# LOCO-Light.net
KiCad netlist of a schematic drawn in EAGLE
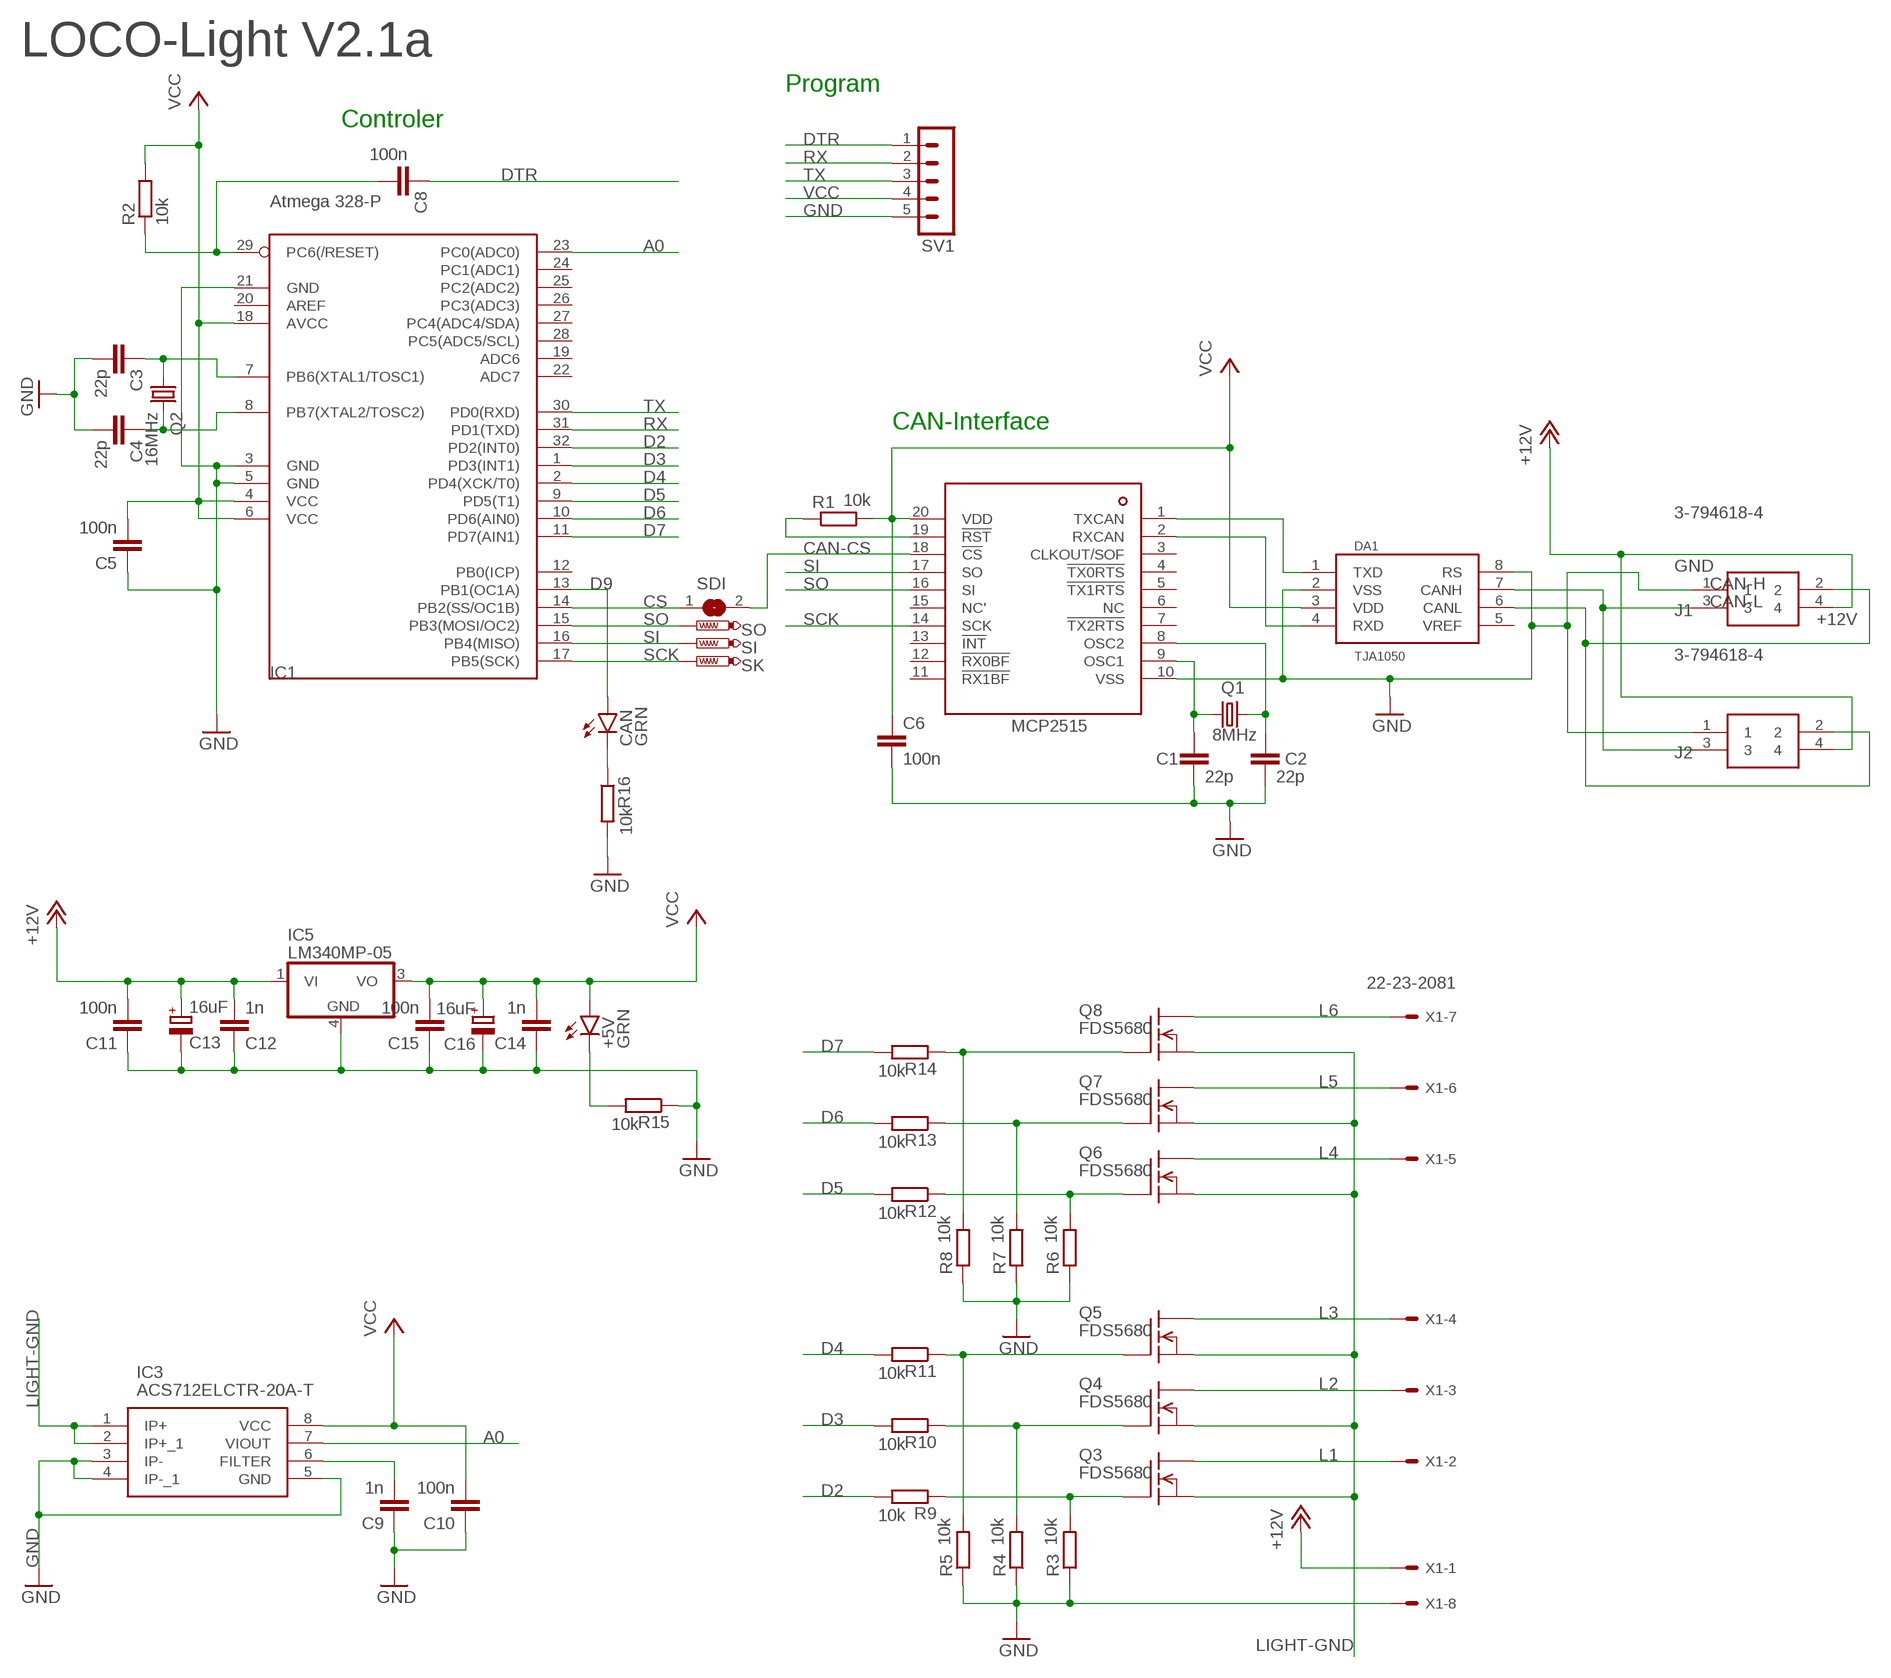
[diagram p0: schematic, sheet 1]

(export (version "E")
  (design (tool "Eeschema 10.0.6"))
  (components
    (comp (ref "+5V")
      (value "GRN")
      (footprint "eagle-import:CHIP-LED0603")
      (libsource (lib "eagle-import") (part "LEDCHIP-LED0603"))
    )
    (comp (ref "C1")
      (value "22p")
      (footprint "eagle-import:C0402K")
      (libsource (lib "eagle-import") (part "C-EUC0402K"))
    )
    (comp (ref "C2")
      (value "22p")
      (footprint "eagle-import:C0402K")
      (libsource (lib "eagle-import") (part "C-EUC0402K"))
    )
    (comp (ref "C3")
      (value "22p")
      (footprint "eagle-import:C0402K")
      (libsource (lib "eagle-import") (part "C-EUC0402K"))
    )
    (comp (ref "C4")
      (value "22p")
      (footprint "eagle-import:C0402K")
      (libsource (lib "eagle-import") (part "C-EUC0402K"))
    )
    (comp (ref "C5")
      (value "100n")
      (footprint "eagle-import:C0402K")
      (libsource (lib "eagle-import") (part "C-EUC0402K"))
    )
    (comp (ref "C6")
      (value "100n")
      (footprint "eagle-import:C0402K")
      (libsource (lib "eagle-import") (part "C-EUC0402K"))
    )
    (comp (ref "C8")
      (value "100n")
      (footprint "eagle-import:C0402K")
      (libsource (lib "eagle-import") (part "C-EUC0402K"))
    )
    (comp (ref "C9")
      (value "1n")
      (footprint "eagle-import:C0402K")
      (libsource (lib "eagle-import") (part "C-EUC0402K"))
    )
    (comp (ref "C10")
      (value "100n")
      (footprint "eagle-import:C0402K")
      (libsource (lib "eagle-import") (part "C-EUC0402K"))
    )
    (comp (ref "C11")
      (value "100n")
      (footprint "eagle-import:C0402K")
      (libsource (lib "eagle-import") (part "C-EUC0402K"))
    )
    (comp (ref "C12")
      (value "1n")
      (footprint "eagle-import:C0402K")
      (libsource (lib "eagle-import") (part "C-EUC0402K"))
    )
    (comp (ref "C13")
      (value "16uF")
      (footprint "eagle-import:A_3216-18W")
      (libsource (lib "eagle-import") (part "CPOL-EUA/3216-18W"))
    )
    (comp (ref "C14")
      (value "1n")
      (footprint "eagle-import:C0402K")
      (libsource (lib "eagle-import") (part "C-EUC0402K"))
    )
    (comp (ref "C15")
      (value "100n")
      (footprint "eagle-import:C0402K")
      (libsource (lib "eagle-import") (part "C-EUC0402K"))
    )
    (comp (ref "C16")
      (value "16uF")
      (footprint "eagle-import:A_3216-18W")
      (libsource (lib "eagle-import") (part "CPOL-EUA/3216-18W"))
    )
    (comp (ref "CAN")
      (value "GRN")
      (footprint "eagle-import:CHIP-LED0603")
      (libsource (lib "eagle-import") (part "LEDCHIP-LED0603"))
    )
    (comp (ref "DA1")
      (value "TJA1050")
      (footprint "eagle-import:SO08")
      (libsource (lib "eagle-import") (part "TJA1050"))
    )
    (comp (ref "IC1")
      (value "Atmega 328-P")
      (footprint "eagle-import:TQFP32-08")
      (fields (field (name "MPN") "ATMEGA8-16AU"))
      (libsource (lib "eagle-import") (part "MEGA8-AI"))
    )
    (comp (ref "IC2")
      (value "MCP2515")
      (footprint "eagle-import:TSSOP20")
      (libsource (lib "eagle-import") (part "MCP2515"))
    )
    (comp (ref "IC3")
      (value "ACS712ELCTR-20A-T")
      (footprint "eagle-import:SOIC127P600X175-8N")
      (fields (field (name "RS_PART_NUMBER") "6807135P"))
      (libsource (lib "eagle-import") (part "ACS712ELCTR-20A-T"))
    )
    (comp (ref "IC5")
      (value "LM340MP-05")
      (footprint "eagle-import:SOT223")
      (libsource (lib "eagle-import") (part "LM340?-MP05"))
    )
    (comp (ref "J1")
      (value "3-794618-4")
      (footprint "eagle-import:SHDRRA4W102P300_2X2_686X892X73")
      (libsource (lib "eagle-import") (part "3-794618-4"))
    )
    (comp (ref "J2")
      (value "3-794618-4")
      (footprint "eagle-import:SHDRRA4W102P300_2X2_686X892X73")
      (libsource (lib "eagle-import") (part "3-794618-4"))
    )
    (comp (ref "Q1")
      (value "8MHz")
      (footprint "eagle-import:HC49_S")
      (libsource (lib "eagle-import") (part "CRYSTALHC49S"))
    )
    (comp (ref "Q2")
      (value "16MHz")
      (footprint "eagle-import:HC49_S")
      (libsource (lib "eagle-import") (part "CRYSTALHC49S"))
    )
    (comp (ref "Q3")
      (value "FDS5680")
      (footprint "eagle-import:SO-8")
      (libsource (lib "eagle-import") (part "FDS5680"))
    )
    (comp (ref "Q4")
      (value "FDS5680")
      (footprint "eagle-import:SO-8")
      (libsource (lib "eagle-import") (part "FDS5680"))
    )
    (comp (ref "Q5")
      (value "FDS5680")
      (footprint "eagle-import:SO-8")
      (libsource (lib "eagle-import") (part "FDS5680"))
    )
    (comp (ref "Q6")
      (value "FDS5680")
      (footprint "eagle-import:SO-8")
      (libsource (lib "eagle-import") (part "FDS5680"))
    )
    (comp (ref "Q7")
      (value "FDS5680")
      (footprint "eagle-import:SO-8")
      (libsource (lib "eagle-import") (part "FDS5680"))
    )
    (comp (ref "Q8")
      (value "FDS5680")
      (footprint "eagle-import:SO-8")
      (libsource (lib "eagle-import") (part "FDS5680"))
    )
    (comp (ref "R1")
      (value "10k")
      (footprint "eagle-import:R0603")
      (libsource (lib "eagle-import") (part "R-EU_R0603"))
    )
    (comp (ref "R2")
      (value "10k")
      (footprint "eagle-import:R0603")
      (libsource (lib "eagle-import") (part "R-EU_R0603"))
    )
    (comp (ref "R3")
      (value "10k")
      (footprint "eagle-import:R0603")
      (libsource (lib "eagle-import") (part "R-EU_R0603"))
    )
    (comp (ref "R4")
      (value "10k")
      (footprint "eagle-import:R0603")
      (libsource (lib "eagle-import") (part "R-EU_R0603"))
    )
    (comp (ref "R5")
      (value "10k")
      (footprint "eagle-import:R0603")
      (libsource (lib "eagle-import") (part "R-EU_R0603"))
    )
    (comp (ref "R6")
      (value "10k")
      (footprint "eagle-import:R0603")
      (libsource (lib "eagle-import") (part "R-EU_R0603"))
    )
    (comp (ref "R7")
      (value "10k")
      (footprint "eagle-import:R0603")
      (libsource (lib "eagle-import") (part "R-EU_R0603"))
    )
    (comp (ref "R8")
      (value "10k")
      (footprint "eagle-import:R0603")
      (libsource (lib "eagle-import") (part "R-EU_R0603"))
    )
    (comp (ref "R9")
      (value "10k")
      (footprint "eagle-import:R0603")
      (libsource (lib "eagle-import") (part "R-EU_R0603"))
    )
    (comp (ref "R10")
      (value "10k")
      (footprint "eagle-import:R0603")
      (libsource (lib "eagle-import") (part "R-EU_R0603"))
    )
    (comp (ref "R11")
      (value "10k")
      (footprint "eagle-import:R0603")
      (libsource (lib "eagle-import") (part "R-EU_R0603"))
    )
    (comp (ref "R12")
      (value "10k")
      (footprint "eagle-import:R0603")
      (libsource (lib "eagle-import") (part "R-EU_R0603"))
    )
    (comp (ref "R13")
      (value "10k")
      (footprint "eagle-import:R0603")
      (libsource (lib "eagle-import") (part "R-EU_R0603"))
    )
    (comp (ref "R14")
      (value "10k")
      (footprint "eagle-import:R0603")
      (libsource (lib "eagle-import") (part "R-EU_R0603"))
    )
    (comp (ref "R15")
      (value "10k")
      (footprint "eagle-import:R0603")
      (libsource (lib "eagle-import") (part "R-EU_R0603"))
    )
    (comp (ref "R16")
      (value "10k")
      (footprint "eagle-import:R0603")
      (libsource (lib "eagle-import") (part "R-EU_R0603"))
    )
    (comp (ref "SDI") (value "SJ") (footprint "eagle-import:SJ") (libsource (lib "eagle-import") (part "SJ")))
    (comp (ref "SI")
      (value "PTR1B1,27")
      (footprint "eagle-import:B1,27")
      (libsource (lib "eagle-import") (part "PTR1B1,27"))
    )
    (comp (ref "SK")
      (value "PTR1B1,27")
      (footprint "eagle-import:B1,27")
      (libsource (lib "eagle-import") (part "PTR1B1,27"))
    )
    (comp (ref "SO")
      (value "PTR1B1,27")
      (footprint "eagle-import:B1,27")
      (libsource (lib "eagle-import") (part "PTR1B1,27"))
    )
    (comp (ref "SV1")
      (value "MA05-1")
      (footprint "eagle-import:MA05-1")
      (libsource (lib "eagle-import") (part "MA05-1"))
    )
    (comp (ref "X1")
      (value "22-23-2081")
      (footprint "eagle-import:22-23-2081")
      (fields (field (name "MF") "MOLEX"))
      (libsource (lib "eagle-import") (part "22-23-2081"))
    )
  )
  (nets
    (net (code "1") (name "+12V") (class "Default")
      (node (ref "C11") (pin "2") (pinfunction "2_2") (pintype "passive"))
      (node (ref "C12") (pin "2") (pinfunction "2_2") (pintype "passive"))
      (node (ref "C13") (pin "+") (pinfunction "+_+") (pintype "passive"))
      (node (ref "IC5") (pin "1") (pinfunction "VI_1") (pintype "input"))
      (node (ref "J1") (pin "4") (pinfunction "4_4") (pintype "bidirectional"))
      (node (ref "J2") (pin "4") (pinfunction "4_4") (pintype "bidirectional"))
      (node (ref "X1") (pin "1") (pinfunction "S_1") (pintype "passive"))
    )
    (net (code "2") (name "A0") (class "Default")
      (node (ref "IC1") (pin "23") (pinfunction "PC0(ADC0)_23") (pintype "bidirectional"))
      (node (ref "IC3") (pin "7") (pinfunction "VIOUT_7") (pintype "bidirectional"))
    )
    (net (code "3") (name "CAN-CS") (class "Default")
      (node (ref "IC2") (pin "18") (pinfunction "~{CS}_18") (pintype "bidirectional"))
      (node (ref "SDI") (pin "2") (pinfunction "2_2") (pintype "passive"))
    )
    (net (code "4") (name "CAN-H") (class "Default")
      (node (ref "DA1") (pin "7") (pinfunction "CANH_7") (pintype "bidirectional"))
      (node (ref "J1") (pin "3") (pinfunction "3_3") (pintype "bidirectional"))
      (node (ref "J2") (pin "3") (pinfunction "3_3") (pintype "bidirectional"))
    )
    (net (code "5") (name "CAN-L") (class "Default")
      (node (ref "DA1") (pin "6") (pinfunction "CANL_6") (pintype "bidirectional"))
      (node (ref "J1") (pin "2") (pinfunction "2_2") (pintype "bidirectional"))
      (node (ref "J2") (pin "2") (pinfunction "2_2") (pintype "bidirectional"))
    )
    (net (code "6") (name "CS") (class "Default")
      (node (ref "IC1") (pin "14") (pinfunction "PB2(SS/OC1B)_14") (pintype "bidirectional"))
      (node (ref "SDI") (pin "1") (pinfunction "1_1") (pintype "passive"))
    )
    (net (code "7") (name "D2") (class "Default")
      (node (ref "IC1") (pin "32") (pinfunction "PD2(INT0)_32") (pintype "bidirectional"))
      (node (ref "R9") (pin "2") (pinfunction "2_2") (pintype "passive"))
    )
    (net (code "8") (name "D3") (class "Default")
      (node (ref "IC1") (pin "1") (pinfunction "PD3(INT1)_1") (pintype "bidirectional"))
      (node (ref "R10") (pin "2") (pinfunction "2_2") (pintype "passive"))
    )
    (net (code "9") (name "D4") (class "Default")
      (node (ref "IC1") (pin "2") (pinfunction "PD4(XCK/T0)_2") (pintype "bidirectional"))
      (node (ref "R11") (pin "2") (pinfunction "2_2") (pintype "passive"))
    )
    (net (code "10") (name "D5") (class "Default")
      (node (ref "IC1") (pin "9") (pinfunction "PD5(T1)_9") (pintype "bidirectional"))
      (node (ref "R12") (pin "2") (pinfunction "2_2") (pintype "passive"))
    )
    (net (code "11") (name "D6") (class "Default")
      (node (ref "IC1") (pin "10") (pinfunction "PD6(AIN0)_10") (pintype "bidirectional"))
      (node (ref "R13") (pin "2") (pinfunction "2_2") (pintype "passive"))
    )
    (net (code "12") (name "D7") (class "Default")
      (node (ref "IC1") (pin "11") (pinfunction "PD7(AIN1)_11") (pintype "bidirectional"))
      (node (ref "R14") (pin "2") (pinfunction "2_2") (pintype "passive"))
    )
    (net (code "13") (name "D9") (class "Default")
      (node (ref "CAN") (pin "A") (pinfunction "A_A") (pintype "passive"))
      (node (ref "IC1") (pin "13") (pinfunction "PB1(OC1A)_13") (pintype "bidirectional"))
    )
    (net (code "14") (name "DTR") (class "Default")
      (node (ref "C8") (pin "1") (pinfunction "1_1") (pintype "passive"))
      (node (ref "SV1") (pin "1") (pinfunction "1_1") (pintype "passive"))
    )
    (net (code "15") (name "GND") (class "Default")
      (node (ref "C1") (pin "2") (pinfunction "2_2") (pintype "passive"))
      (node (ref "C10") (pin "1") (pinfunction "1_1") (pintype "passive"))
      (node (ref "C11") (pin "1") (pinfunction "1_1") (pintype "passive"))
      (node (ref "C12") (pin "1") (pinfunction "1_1") (pintype "passive"))
      (node (ref "C13") (pin "-") (pinfunction "-_-") (pintype "passive"))
      (node (ref "C14") (pin "1") (pinfunction "1_1") (pintype "passive"))
      (node (ref "C15") (pin "1") (pinfunction "1_1") (pintype "passive"))
      (node (ref "C16") (pin "-") (pinfunction "-_-") (pintype "passive"))
      (node (ref "C2") (pin "2") (pinfunction "2_2") (pintype "passive"))
      (node (ref "C3") (pin "2") (pinfunction "2_2") (pintype "passive"))
      (node (ref "C4") (pin "2") (pinfunction "2_2") (pintype "passive"))
      (node (ref "C5") (pin "1") (pinfunction "1_1") (pintype "passive"))
      (node (ref "C6") (pin "2") (pinfunction "2_2") (pintype "passive"))
      (node (ref "C9") (pin "1") (pinfunction "1_1") (pintype "passive"))
      (node (ref "DA1") (pin "2") (pinfunction "VSS_2") (pintype "power_in"))
      (node (ref "DA1") (pin "8") (pinfunction "RS_8") (pintype "input"))
      (node (ref "IC1") (pin "21") (pinfunction "GND_21") (pintype "power_in"))
      (node (ref "IC1") (pin "3") (pinfunction "GND_3") (pintype "power_in"))
      (node (ref "IC1") (pin "5") (pinfunction "GND_5") (pintype "power_in"))
      (node (ref "IC2") (pin "10") (pinfunction "VSS_10") (pintype "bidirectional"))
      (node (ref "IC3") (pin "3") (pinfunction "IP-_3") (pintype "bidirectional"))
      (node (ref "IC3") (pin "4") (pinfunction "IP-_1_4") (pintype "bidirectional"))
      (node (ref "IC3") (pin "5") (pinfunction "GND_5") (pintype "power_in"))
      (node (ref "IC5") (pin "4") (pinfunction "GND_4") (pintype "passive"))
      (node (ref "J1") (pin "1") (pinfunction "1_1") (pintype "bidirectional"))
      (node (ref "J2") (pin "1") (pinfunction "1_1") (pintype "bidirectional"))
      (node (ref "R15") (pin "1") (pinfunction "1_1") (pintype "passive"))
      (node (ref "R16") (pin "2") (pinfunction "2_2") (pintype "passive"))
      (node (ref "R3") (pin "1") (pinfunction "1_1") (pintype "passive"))
      (node (ref "R4") (pin "1") (pinfunction "1_1") (pintype "passive"))
      (node (ref "R5") (pin "1") (pinfunction "1_1") (pintype "passive"))
      (node (ref "R6") (pin "1") (pinfunction "1_1") (pintype "passive"))
      (node (ref "R7") (pin "1") (pinfunction "1_1") (pintype "passive"))
      (node (ref "R8") (pin "1") (pinfunction "1_1") (pintype "passive"))
      (node (ref "SV1") (pin "5") (pinfunction "5_5") (pintype "passive"))
      (node (ref "X1") (pin "8") (pinfunction "S_8") (pintype "passive"))
    )
    (net (code "16") (name "L1") (class "Default")
      (node (ref "Q3") (pin "5") (pinfunction "D_5") (pintype "passive"))
      (node (ref "Q3") (pin "6") (pinfunction "D_6") (pintype "passive"))
      (node (ref "Q3") (pin "7") (pinfunction "D_7") (pintype "passive"))
      (node (ref "Q3") (pin "8") (pinfunction "D_8") (pintype "passive"))
      (node (ref "X1") (pin "2") (pinfunction "S_2") (pintype "passive"))
    )
    (net (code "17") (name "L2") (class "Default")
      (node (ref "Q4") (pin "5") (pinfunction "D_5") (pintype "passive"))
      (node (ref "Q4") (pin "6") (pinfunction "D_6") (pintype "passive"))
      (node (ref "Q4") (pin "7") (pinfunction "D_7") (pintype "passive"))
      (node (ref "Q4") (pin "8") (pinfunction "D_8") (pintype "passive"))
      (node (ref "X1") (pin "3") (pinfunction "S_3") (pintype "passive"))
    )
    (net (code "18") (name "L3") (class "Default")
      (node (ref "Q5") (pin "5") (pinfunction "D_5") (pintype "passive"))
      (node (ref "Q5") (pin "6") (pinfunction "D_6") (pintype "passive"))
      (node (ref "Q5") (pin "7") (pinfunction "D_7") (pintype "passive"))
      (node (ref "Q5") (pin "8") (pinfunction "D_8") (pintype "passive"))
      (node (ref "X1") (pin "4") (pinfunction "S_4") (pintype "passive"))
    )
    (net (code "19") (name "L4") (class "Default")
      (node (ref "Q6") (pin "5") (pinfunction "D_5") (pintype "passive"))
      (node (ref "Q6") (pin "6") (pinfunction "D_6") (pintype "passive"))
      (node (ref "Q6") (pin "7") (pinfunction "D_7") (pintype "passive"))
      (node (ref "Q6") (pin "8") (pinfunction "D_8") (pintype "passive"))
      (node (ref "X1") (pin "5") (pinfunction "S_5") (pintype "passive"))
    )
    (net (code "20") (name "L5") (class "Default")
      (node (ref "Q7") (pin "5") (pinfunction "D_5") (pintype "passive"))
      (node (ref "Q7") (pin "6") (pinfunction "D_6") (pintype "passive"))
      (node (ref "Q7") (pin "7") (pinfunction "D_7") (pintype "passive"))
      (node (ref "Q7") (pin "8") (pinfunction "D_8") (pintype "passive"))
      (node (ref "X1") (pin "6") (pinfunction "S_6") (pintype "passive"))
    )
    (net (code "21") (name "L6") (class "Default")
      (node (ref "Q8") (pin "5") (pinfunction "D_5") (pintype "passive"))
      (node (ref "Q8") (pin "6") (pinfunction "D_6") (pintype "passive"))
      (node (ref "Q8") (pin "7") (pinfunction "D_7") (pintype "passive"))
      (node (ref "Q8") (pin "8") (pinfunction "D_8") (pintype "passive"))
      (node (ref "X1") (pin "7") (pinfunction "S_7") (pintype "passive"))
    )
    (net (code "22") (name "LIGHT-GND") (class "Default")
      (node (ref "IC3") (pin "1") (pinfunction "IP+_1") (pintype "bidirectional"))
      (node (ref "IC3") (pin "2") (pinfunction "IP+_1_2") (pintype "bidirectional"))
      (node (ref "Q3") (pin "1") (pinfunction "S_1") (pintype "passive"))
      (node (ref "Q3") (pin "2") (pinfunction "S_2") (pintype "passive"))
      (node (ref "Q3") (pin "3") (pinfunction "S_3") (pintype "passive"))
      (node (ref "Q4") (pin "1") (pinfunction "S_1") (pintype "passive"))
      (node (ref "Q4") (pin "2") (pinfunction "S_2") (pintype "passive"))
      (node (ref "Q4") (pin "3") (pinfunction "S_3") (pintype "passive"))
      (node (ref "Q5") (pin "1") (pinfunction "S_1") (pintype "passive"))
      (node (ref "Q5") (pin "2") (pinfunction "S_2") (pintype "passive"))
      (node (ref "Q5") (pin "3") (pinfunction "S_3") (pintype "passive"))
      (node (ref "Q6") (pin "1") (pinfunction "S_1") (pintype "passive"))
      (node (ref "Q6") (pin "2") (pinfunction "S_2") (pintype "passive"))
      (node (ref "Q6") (pin "3") (pinfunction "S_3") (pintype "passive"))
      (node (ref "Q7") (pin "1") (pinfunction "S_1") (pintype "passive"))
      (node (ref "Q7") (pin "2") (pinfunction "S_2") (pintype "passive"))
      (node (ref "Q7") (pin "3") (pinfunction "S_3") (pintype "passive"))
      (node (ref "Q8") (pin "1") (pinfunction "S_1") (pintype "passive"))
      (node (ref "Q8") (pin "2") (pinfunction "S_2") (pintype "passive"))
      (node (ref "Q8") (pin "3") (pinfunction "S_3") (pintype "passive"))
    )
    (net (code "23") (name "Net-(+5V-PadC)") (class "Default")
      (node (ref "+5V") (pin "C") (pinfunction "C_C") (pintype "passive"))
      (node (ref "R15") (pin "2") (pinfunction "2_2") (pintype "passive"))
    )
    (net (code "24") (name "Net-(CAN-PadC)") (class "Default")
      (node (ref "CAN") (pin "C") (pinfunction "C_C") (pintype "passive"))
      (node (ref "R16") (pin "1") (pinfunction "1_1") (pintype "passive"))
    )
    (net (code "25") (name "Net-(DA1-RXD)") (class "Default")
      (node (ref "DA1") (pin "4") (pinfunction "RXD_4") (pintype "output"))
      (node (ref "IC2") (pin "2") (pinfunction "RXCAN_2") (pintype "bidirectional"))
    )
    (net (code "26") (name "Net-(DA1-TXD)") (class "Default")
      (node (ref "DA1") (pin "1") (pinfunction "TXD_1") (pintype "input"))
      (node (ref "IC2") (pin "1") (pinfunction "TXCAN_1") (pintype "bidirectional"))
    )
    (net (code "27") (name "Net-(IC1-PB6(XTAL1{slash}TOSC1))") (class "Default")
      (node (ref "C3") (pin "1") (pinfunction "1_1") (pintype "passive"))
      (node (ref "IC1") (pin "7") (pinfunction "PB6(XTAL1/TOSC1)_7") (pintype "bidirectional"))
      (node (ref "Q2") (pin "1") (pinfunction "1_1") (pintype "passive"))
    )
    (net (code "28") (name "Net-(IC1-PB7(XTAL2{slash}TOSC2))") (class "Default")
      (node (ref "C4") (pin "1") (pinfunction "1_1") (pintype "passive"))
      (node (ref "IC1") (pin "8") (pinfunction "PB7(XTAL2/TOSC2)_8") (pintype "bidirectional"))
      (node (ref "Q2") (pin "2") (pinfunction "2_2") (pintype "passive"))
    )
    (net (code "29") (name "Net-(IC1-PC6({slash}RESET))") (class "Default")
      (node (ref "C8") (pin "2") (pinfunction "2_2") (pintype "passive"))
      (node (ref "IC1") (pin "29") (pinfunction "PC6(/RESET)_29") (pintype "bidirectional"))
      (node (ref "R2") (pin "1") (pinfunction "1_1") (pintype "passive"))
    )
    (net (code "30") (name "Net-(IC2-OSC1)") (class "Default")
      (node (ref "C1") (pin "1") (pinfunction "1_1") (pintype "passive"))
      (node (ref "IC2") (pin "9") (pinfunction "OSC1_9") (pintype "bidirectional"))
      (node (ref "Q1") (pin "1") (pinfunction "1_1") (pintype "passive"))
    )
    (net (code "31") (name "Net-(IC2-OSC2)") (class "Default")
      (node (ref "C2") (pin "1") (pinfunction "1_1") (pintype "passive"))
      (node (ref "IC2") (pin "8") (pinfunction "OSC2_8") (pintype "bidirectional"))
      (node (ref "Q1") (pin "2") (pinfunction "2_2") (pintype "passive"))
    )
    (net (code "32") (name "Net-(IC2-~{RST})") (class "Default")
      (node (ref "IC2") (pin "19") (pinfunction "~{RST}_19") (pintype "bidirectional"))
      (node (ref "R1") (pin "1") (pinfunction "1_1") (pintype "passive"))
    )
    (net (code "33") (name "Net-(IC3-FILTER)") (class "Default")
      (node (ref "C9") (pin "2") (pinfunction "2_2") (pintype "passive"))
      (node (ref "IC3") (pin "6") (pinfunction "FILTER_6") (pintype "bidirectional"))
    )
    (net (code "34") (name "Net-(Q3-G)") (class "Default")
      (node (ref "Q3") (pin "4") (pinfunction "G_4") (pintype "passive"))
      (node (ref "R3") (pin "2") (pinfunction "2_2") (pintype "passive"))
      (node (ref "R9") (pin "1") (pinfunction "1_1") (pintype "passive"))
    )
    (net (code "35") (name "Net-(Q4-G)") (class "Default")
      (node (ref "Q4") (pin "4") (pinfunction "G_4") (pintype "passive"))
      (node (ref "R10") (pin "1") (pinfunction "1_1") (pintype "passive"))
      (node (ref "R4") (pin "2") (pinfunction "2_2") (pintype "passive"))
    )
    (net (code "36") (name "Net-(Q5-G)") (class "Default")
      (node (ref "Q5") (pin "4") (pinfunction "G_4") (pintype "passive"))
      (node (ref "R11") (pin "1") (pinfunction "1_1") (pintype "passive"))
      (node (ref "R5") (pin "2") (pinfunction "2_2") (pintype "passive"))
    )
    (net (code "37") (name "Net-(Q6-G)") (class "Default")
      (node (ref "Q6") (pin "4") (pinfunction "G_4") (pintype "passive"))
      (node (ref "R12") (pin "1") (pinfunction "1_1") (pintype "passive"))
      (node (ref "R6") (pin "2") (pinfunction "2_2") (pintype "passive"))
    )
    (net (code "38") (name "Net-(Q7-G)") (class "Default")
      (node (ref "Q7") (pin "4") (pinfunction "G_4") (pintype "passive"))
      (node (ref "R13") (pin "1") (pinfunction "1_1") (pintype "passive"))
      (node (ref "R7") (pin "2") (pinfunction "2_2") (pintype "passive"))
    )
    (net (code "39") (name "Net-(Q8-G)") (class "Default")
      (node (ref "Q8") (pin "4") (pinfunction "G_4") (pintype "passive"))
      (node (ref "R14") (pin "1") (pinfunction "1_1") (pintype "passive"))
      (node (ref "R8") (pin "2") (pinfunction "2_2") (pintype "passive"))
    )
    (net (code "40") (name "RX") (class "Default")
      (node (ref "IC1") (pin "31") (pinfunction "PD1(TXD)_31") (pintype "bidirectional"))
      (node (ref "SV1") (pin "2") (pinfunction "2_2") (pintype "passive"))
    )
    (net (code "41") (name "SCK") (class "Default")
      (node (ref "IC1") (pin "17") (pinfunction "PB5(SCK)_17") (pintype "bidirectional"))
      (node (ref "IC2") (pin "14") (pinfunction "SCK_14") (pintype "bidirectional"))
      (node (ref "SK") (pin "TP") (pinfunction "TP_TP") (pintype "input"))
    )
    (net (code "42") (name "SI") (class "Default")
      (node (ref "IC1") (pin "16") (pinfunction "PB4(MISO)_16") (pintype "bidirectional"))
      (node (ref "IC2") (pin "17") (pinfunction "SO_17") (pintype "bidirectional"))
      (node (ref "SI") (pin "TP") (pinfunction "TP_TP") (pintype "input"))
    )
    (net (code "43") (name "SO") (class "Default")
      (node (ref "IC1") (pin "15") (pinfunction "PB3(MOSI/OC2)_15") (pintype "bidirectional"))
      (node (ref "IC2") (pin "16") (pinfunction "SI_16") (pintype "bidirectional"))
      (node (ref "SO") (pin "TP") (pinfunction "TP_TP") (pintype "input"))
    )
    (net (code "44") (name "TX") (class "Default")
      (node (ref "IC1") (pin "30") (pinfunction "PD0(RXD)_30") (pintype "bidirectional"))
      (node (ref "SV1") (pin "3") (pinfunction "3_3") (pintype "passive"))
    )
    (net (code "45") (name "VCC") (class "Default")
      (node (ref "+5V") (pin "A") (pinfunction "A_A") (pintype "passive"))
      (node (ref "C10") (pin "2") (pinfunction "2_2") (pintype "passive"))
      (node (ref "C14") (pin "2") (pinfunction "2_2") (pintype "passive"))
      (node (ref "C15") (pin "2") (pinfunction "2_2") (pintype "passive"))
      (node (ref "C16") (pin "+") (pinfunction "+_+") (pintype "passive"))
      (node (ref "C5") (pin "2") (pinfunction "2_2") (pintype "passive"))
      (node (ref "C6") (pin "1") (pinfunction "1_1") (pintype "passive"))
      (node (ref "DA1") (pin "3") (pinfunction "VDD_3") (pintype "power_in"))
      (node (ref "IC1") (pin "18") (pinfunction "AVCC_18") (pintype "power_in"))
      (node (ref "IC1") (pin "4") (pinfunction "VCC_4") (pintype "power_in"))
      (node (ref "IC1") (pin "6") (pinfunction "VCC_6") (pintype "power_in"))
      (node (ref "IC2") (pin "20") (pinfunction "VDD_20") (pintype "bidirectional"))
      (node (ref "IC3") (pin "8") (pinfunction "VCC_8") (pintype "power_in"))
      (node (ref "IC5") (pin "3") (pinfunction "VO_3") (pintype "passive"))
      (node (ref "R1") (pin "2") (pinfunction "2_2") (pintype "passive"))
      (node (ref "R2") (pin "2") (pinfunction "2_2") (pintype "passive"))
      (node (ref "SV1") (pin "4") (pinfunction "4_4") (pintype "passive"))
    )
    (net (code "46") (name "unconnected-(DA1-VREF-Pad5)") (class "Default")
      (node (ref "DA1") (pin "5") (pinfunction "VREF_5") (pintype "passive"))
    )
    (net (code "47") (name "unconnected-(IC1-ADC6-Pad19)") (class "Default")
      (node (ref "IC1") (pin "19") (pinfunction "ADC6_19") (pintype "bidirectional"))
    )
    (net (code "48") (name "unconnected-(IC1-ADC7-Pad22)") (class "Default")
      (node (ref "IC1") (pin "22") (pinfunction "ADC7_22") (pintype "bidirectional"))
    )
    (net (code "49") (name "unconnected-(IC1-AREF-Pad20)") (class "Default")
      (node (ref "IC1") (pin "20") (pinfunction "AREF_20") (pintype "passive"))
    )
    (net (code "50") (name "unconnected-(IC1-PB0(ICP)-Pad12)") (class "Default")
      (node (ref "IC1") (pin "12") (pinfunction "PB0(ICP)_12") (pintype "bidirectional"))
    )
    (net (code "51") (name "unconnected-(IC1-PC1(ADC1)-Pad24)") (class "Default")
      (node (ref "IC1") (pin "24") (pinfunction "PC1(ADC1)_24") (pintype "bidirectional"))
    )
    (net (code "52") (name "unconnected-(IC1-PC2(ADC2)-Pad25)") (class "Default")
      (node (ref "IC1") (pin "25") (pinfunction "PC2(ADC2)_25") (pintype "bidirectional"))
    )
    (net (code "53") (name "unconnected-(IC1-PC3(ADC3)-Pad26)") (class "Default")
      (node (ref "IC1") (pin "26") (pinfunction "PC3(ADC3)_26") (pintype "bidirectional"))
    )
    (net (code "54") (name "unconnected-(IC1-PC4(ADC4{slash}SDA)-Pad27)") (class "Default")
      (node (ref "IC1") (pin "27") (pinfunction "PC4(ADC4/SDA)_27") (pintype "bidirectional"))
    )
    (net (code "55") (name "unconnected-(IC1-PC5(ADC5{slash}SCL)-Pad28)") (class "Default")
      (node (ref "IC1") (pin "28") (pinfunction "PC5(ADC5/SCL)_28") (pintype "bidirectional"))
    )
    (net (code "56") (name "unconnected-(IC2-CLKOUT{slash}SOF-Pad3)") (class "Default")
      (node (ref "IC2") (pin "3") (pinfunction "CLKOUT/SOF_3") (pintype "bidirectional"))
    )
    (net (code "57") (name "unconnected-(IC2-NC'-Pad15)") (class "Default")
      (node (ref "IC2") (pin "15") (pinfunction "NC'_15") (pintype "bidirectional"))
    )
    (net (code "58") (name "unconnected-(IC2-NC-Pad6)") (class "Default")
      (node (ref "IC2") (pin "6") (pinfunction "NC_6") (pintype "bidirectional"))
    )
    (net (code "59") (name "unconnected-(IC2-~{INT}-Pad13)") (class "Default")
      (node (ref "IC2") (pin "13") (pinfunction "~{INT}_13") (pintype "bidirectional"))
    )
    (net (code "60") (name "unconnected-(IC2-~{RX0BF}-Pad12)") (class "Default")
      (node (ref "IC2") (pin "12") (pinfunction "~{RX0BF}_12") (pintype "bidirectional"))
    )
    (net (code "61") (name "unconnected-(IC2-~{RX1BF}-Pad11)") (class "Default")
      (node (ref "IC2") (pin "11") (pinfunction "~{RX1BF}_11") (pintype "bidirectional"))
    )
    (net (code "62") (name "unconnected-(IC2-~{TX0RTS}-Pad4)") (class "Default")
      (node (ref "IC2") (pin "4") (pinfunction "~{TX0RTS}_4") (pintype "bidirectional"))
    )
    (net (code "63") (name "unconnected-(IC2-~{TX1RTS}-Pad5)") (class "Default")
      (node (ref "IC2") (pin "5") (pinfunction "~{TX1RTS}_5") (pintype "bidirectional"))
    )
    (net (code "64") (name "unconnected-(IC2-~{TX2RTS}-Pad7)") (class "Default")
      (node (ref "IC2") (pin "7") (pinfunction "~{TX2RTS}_7") (pintype "bidirectional"))
    )
  )
)
